# MCU.net
KiCad netlist of a schematic drawn in Altium Designer
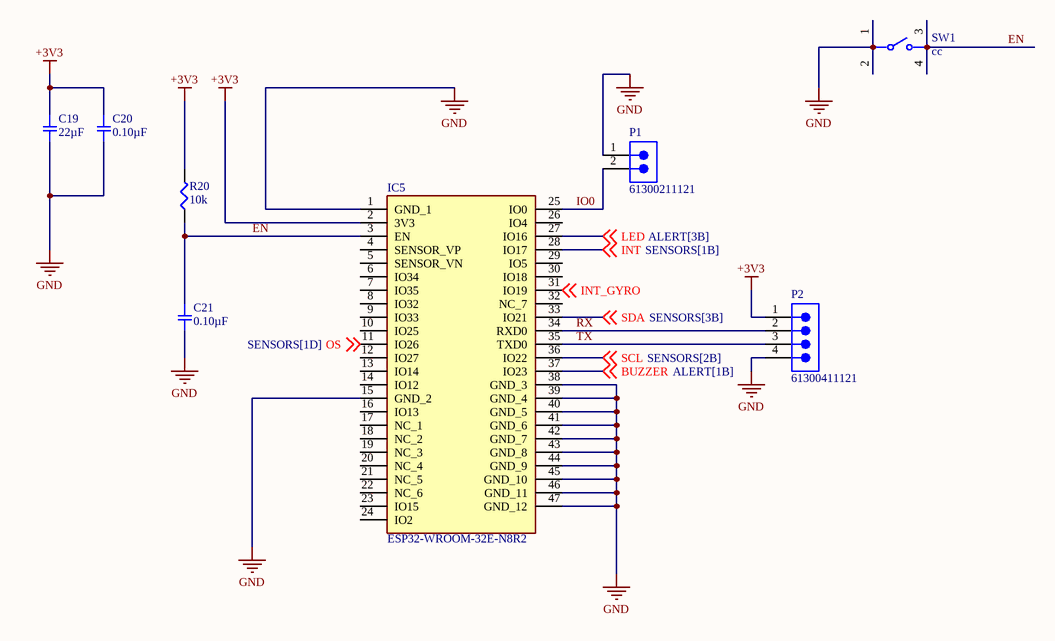
[diagram p0: MCU.SchDoc]

(export (version "E")
  (design (tool "Eeschema 10.0.6"))
  (components
    (comp (ref "C19")
      (value "22µF")
      (footprint "SMD-0603C")
      (description "CAP CER 22UF 6.3V X5R 0603")
      (fields
        (field (name "DIGI-KEY PART NUMBER") "490-10988-1-ND")
        (field (name "PART NUMBER") "ZRB18AR60J226ME01L")
      )
      (libsource (lib "capacitor_murata_0603") (part "ZRB18AR60J226ME01L"))
    )
    (comp (ref "C20")
      (value "0.10µF")
      (footprint "SMD-0603C")
      (description "CAP CER 0.1UF 16V X7R 0603")
      (fields
        (field (name "DIGI-KEY PART NUMBER") "490-5796-1-ND")
        (field (name "PART NUMBER") "GCJ188R71C104KA01D")
      )
      (libsource (lib "capacitor_murata_0603") (part "GCJ188R71C104KA01D"))
    )
    (comp (ref "C21")
      (value "0.10µF")
      (footprint "SMD-0402C")
      (description "CAP CER 0.1UF 16V X7R 0402")
      (fields
        (field (name "DIGI-KEY PART NUMBER") "490-4759-1-ND")
        (field (name "PART NUMBER") "GCM155R71C104KA55D")
      )
      (libsource (lib "capacitor_murata_0402") (part "GCM155R71C104KA55D"))
    )
    (comp (ref "IC5")
      (value "ESP32-WROOM-32E-N8R2")
      (footprint "SamacSys:ESP32WROOM32EN8R2")
      (description "Integrated Circuit")
      (fields (field (name "MOUSER PART NUMBER") "356-ESP32WRM32EN8R2"))
      (libsource (lib "*") (part "ESP32-WROOM-32E-N8R2"))
    )
    (comp (ref "P1")
      (value "61300211121")
      (footprint "61300211121")
      (libsource (lib "Altium Content Vault") (part "Header_Male_1R_02P"))
    )
    (comp (ref "P2")
      (value "61300411121")
      (footprint "61300411121")
      (libsource (lib "Altium Content Vault") (part "Header_Male_1R_04P"))
    )
    (comp (ref "R20")
      (value "10k")
      (footprint "SMD-0402-RES")
      (description "RES SMD 10K OHM 5% 1/10W 0402")
      (fields (field (name "PART NUMBER") "ERJ-2GEJ103X") (field (name "DIGI-KEY PART NUMBER") "P10KJCT-ND"))
      (libsource (lib "Panasonic_ERJ_0402") (part "ERJ-2GEJ103X"))
    )
    (comp (ref "SW1")
      (value "cc")
      (footprint "FP-TL3305AF260QG-MFG")
      (description "SWITCH TACTILE SPST-NO 50MA 12V")
      (libsource (lib "Altium Content Vault") (part "b8895f3f4cefb76e1819d2863dba89b"))
    )
  )
  (nets
    (net (code "1") (name "+3V3") (class "Default")
      (node (ref "C19") (pin "1") (pinfunction "1_1") (pintype "passive"))
      (node (ref "C20") (pin "1") (pinfunction "1_1") (pintype "passive"))
      (node (ref "IC5") (pin "2") (pinfunction "3V3_2") (pintype "passive"))
      (node (ref "P2") (pin "1") (pinfunction "1_1") (pintype "passive"))
      (node (ref "R20") (pin "2") (pinfunction "2_2") (pintype "passive"))
    )
    (net (code "2") (name "/EN") (class "Default")
      (node (ref "C21") (pin "1") (pinfunction "1_1") (pintype "passive"))
      (node (ref "IC5") (pin "3") (pinfunction "EN_3") (pintype "passive"))
      (node (ref "R20") (pin "1") (pinfunction "1_1") (pintype "passive"))
      (node (ref "SW1") (pin "3") (pinfunction "3_3") (pintype "passive"))
      (node (ref "SW1") (pin "4") (pinfunction "4_4") (pintype "passive"))
    )
    (net (code "3") (name "/IO0") (class "Default")
      (node (ref "IC5") (pin "25") (pinfunction "IO0_25") (pintype "passive"))
      (node (ref "P1") (pin "2") (pinfunction "2_2") (pintype "passive"))
    )
    (net (code "4") (name "/RX") (class "Default")
      (node (ref "IC5") (pin "34") (pinfunction "RXD0_34") (pintype "passive"))
      (node (ref "P2") (pin "2") (pinfunction "2_2") (pintype "passive"))
    )
    (net (code "5") (name "/TX") (class "Default")
      (node (ref "IC5") (pin "35") (pinfunction "TXD0_35") (pintype "passive"))
      (node (ref "P2") (pin "3") (pinfunction "3_3") (pintype "passive"))
    )
    (net (code "6") (name "BUZZER") (class "Default")
      (node (ref "IC5") (pin "37") (pinfunction "IO23_37") (pintype "passive"))
    )
    (net (code "7") (name "GND") (class "Default")
      (node (ref "C19") (pin "2") (pinfunction "2_2") (pintype "passive"))
      (node (ref "C20") (pin "2") (pinfunction "2_2") (pintype "passive"))
      (node (ref "C21") (pin "2") (pinfunction "2_2") (pintype "passive"))
      (node (ref "IC5") (pin "1") (pinfunction "GND_1_1") (pintype "passive"))
      (node (ref "IC5") (pin "15") (pinfunction "GND_2_15") (pintype "passive"))
      (node (ref "IC5") (pin "38") (pinfunction "GND_3_38") (pintype "passive"))
      (node (ref "IC5") (pin "39") (pinfunction "GND_4_39") (pintype "passive"))
      (node (ref "IC5") (pin "40") (pinfunction "GND_5_40") (pintype "passive"))
      (node (ref "IC5") (pin "41") (pinfunction "GND_6_41") (pintype "passive"))
      (node (ref "IC5") (pin "42") (pinfunction "GND_7_42") (pintype "passive"))
      (node (ref "IC5") (pin "43") (pinfunction "GND_8_43") (pintype "passive"))
      (node (ref "IC5") (pin "44") (pinfunction "GND_9_44") (pintype "passive"))
      (node (ref "IC5") (pin "45") (pinfunction "GND_10_45") (pintype "passive"))
      (node (ref "IC5") (pin "46") (pinfunction "GND_11_46") (pintype "passive"))
      (node (ref "IC5") (pin "47") (pinfunction "GND_12_47") (pintype "passive"))
      (node (ref "P1") (pin "1") (pinfunction "1_1") (pintype "passive"))
      (node (ref "P2") (pin "4") (pinfunction "4_4") (pintype "passive"))
      (node (ref "SW1") (pin "1") (pinfunction "1_1") (pintype "passive"))
      (node (ref "SW1") (pin "2") (pinfunction "2_2") (pintype "passive"))
    )
    (net (code "8") (name "INT") (class "Default")
      (node (ref "IC5") (pin "28") (pinfunction "IO17_28") (pintype "passive"))
    )
    (net (code "9") (name "INT_GYRO") (class "Default")
      (node (ref "IC5") (pin "31") (pinfunction "IO19_31") (pintype "passive"))
    )
    (net (code "10") (name "LED") (class "Default")
      (node (ref "IC5") (pin "27") (pinfunction "IO16_27") (pintype "passive"))
    )
    (net (code "11") (name "OS") (class "Default")
      (node (ref "IC5") (pin "11") (pinfunction "IO26_11") (pintype "passive"))
    )
    (net (code "12") (name "SCL") (class "Default")
      (node (ref "IC5") (pin "36") (pinfunction "IO22_36") (pintype "passive"))
    )
    (net (code "13") (name "SDA") (class "Default")
      (node (ref "IC5") (pin "33") (pinfunction "IO21_33") (pintype "passive"))
    )
    (net (code "14") (name "unconnected-(IC5-IO2-Pad24)") (class "Default")
      (node (ref "IC5") (pin "24") (pinfunction "IO2_24") (pintype "passive"))
    )
    (net (code "15") (name "unconnected-(IC5-IO4-Pad26)") (class "Default")
      (node (ref "IC5") (pin "26") (pinfunction "IO4_26") (pintype "passive"))
    )
    (net (code "16") (name "unconnected-(IC5-IO5-Pad29)") (class "Default")
      (node (ref "IC5") (pin "29") (pinfunction "IO5_29") (pintype "passive"))
    )
    (net (code "17") (name "unconnected-(IC5-IO12-Pad14)") (class "Default")
      (node (ref "IC5") (pin "14") (pinfunction "IO12_14") (pintype "passive"))
    )
    (net (code "18") (name "unconnected-(IC5-IO13-Pad16)") (class "Default")
      (node (ref "IC5") (pin "16") (pinfunction "IO13_16") (pintype "passive"))
    )
    (net (code "19") (name "unconnected-(IC5-IO14-Pad13)") (class "Default")
      (node (ref "IC5") (pin "13") (pinfunction "IO14_13") (pintype "passive"))
    )
    (net (code "20") (name "unconnected-(IC5-IO15-Pad23)") (class "Default")
      (node (ref "IC5") (pin "23") (pinfunction "IO15_23") (pintype "passive"))
    )
    (net (code "21") (name "unconnected-(IC5-IO18-Pad30)") (class "Default")
      (node (ref "IC5") (pin "30") (pinfunction "IO18_30") (pintype "passive"))
    )
    (net (code "22") (name "unconnected-(IC5-IO25-Pad10)") (class "Default")
      (node (ref "IC5") (pin "10") (pinfunction "IO25_10") (pintype "passive"))
    )
    (net (code "23") (name "unconnected-(IC5-IO27-Pad12)") (class "Default")
      (node (ref "IC5") (pin "12") (pinfunction "IO27_12") (pintype "passive"))
    )
    (net (code "24") (name "unconnected-(IC5-IO32-Pad8)") (class "Default")
      (node (ref "IC5") (pin "8") (pinfunction "IO32_8") (pintype "passive"))
    )
    (net (code "25") (name "unconnected-(IC5-IO33-Pad9)") (class "Default")
      (node (ref "IC5") (pin "9") (pinfunction "IO33_9") (pintype "passive"))
    )
    (net (code "26") (name "unconnected-(IC5-IO34-Pad6)") (class "Default")
      (node (ref "IC5") (pin "6") (pinfunction "IO34_6") (pintype "passive"))
    )
    (net (code "27") (name "unconnected-(IC5-IO35-Pad7)") (class "Default")
      (node (ref "IC5") (pin "7") (pinfunction "IO35_7") (pintype "passive"))
    )
    (net (code "28") (name "unconnected-(IC5-NC_1-Pad17)") (class "Default")
      (node (ref "IC5") (pin "17") (pinfunction "NC_1_17") (pintype "passive"))
    )
    (net (code "29") (name "unconnected-(IC5-NC_2-Pad18)") (class "Default")
      (node (ref "IC5") (pin "18") (pinfunction "NC_2_18") (pintype "passive"))
    )
    (net (code "30") (name "unconnected-(IC5-NC_3-Pad19)") (class "Default")
      (node (ref "IC5") (pin "19") (pinfunction "NC_3_19") (pintype "passive"))
    )
    (net (code "31") (name "unconnected-(IC5-NC_4-Pad20)") (class "Default")
      (node (ref "IC5") (pin "20") (pinfunction "NC_4_20") (pintype "passive"))
    )
    (net (code "32") (name "unconnected-(IC5-NC_5-Pad21)") (class "Default")
      (node (ref "IC5") (pin "21") (pinfunction "NC_5_21") (pintype "passive"))
    )
    (net (code "33") (name "unconnected-(IC5-NC_6-Pad22)") (class "Default")
      (node (ref "IC5") (pin "22") (pinfunction "NC_6_22") (pintype "passive"))
    )
    (net (code "34") (name "unconnected-(IC5-NC_7-Pad32)") (class "Default")
      (node (ref "IC5") (pin "32") (pinfunction "NC_7_32") (pintype "passive"))
    )
    (net (code "35") (name "unconnected-(IC5-SENSOR_VN-Pad5)") (class "Default")
      (node (ref "IC5") (pin "5") (pinfunction "SENSOR_VN_5") (pintype "passive"))
    )
    (net (code "36") (name "unconnected-(IC5-SENSOR_VP-Pad4)") (class "Default")
      (node (ref "IC5") (pin "4") (pinfunction "SENSOR_VP_4") (pintype "passive"))
    )
  )
)
